# Mouse-Schematic_copy.net
KiCad netlist of a schematic drawn in EAGLE
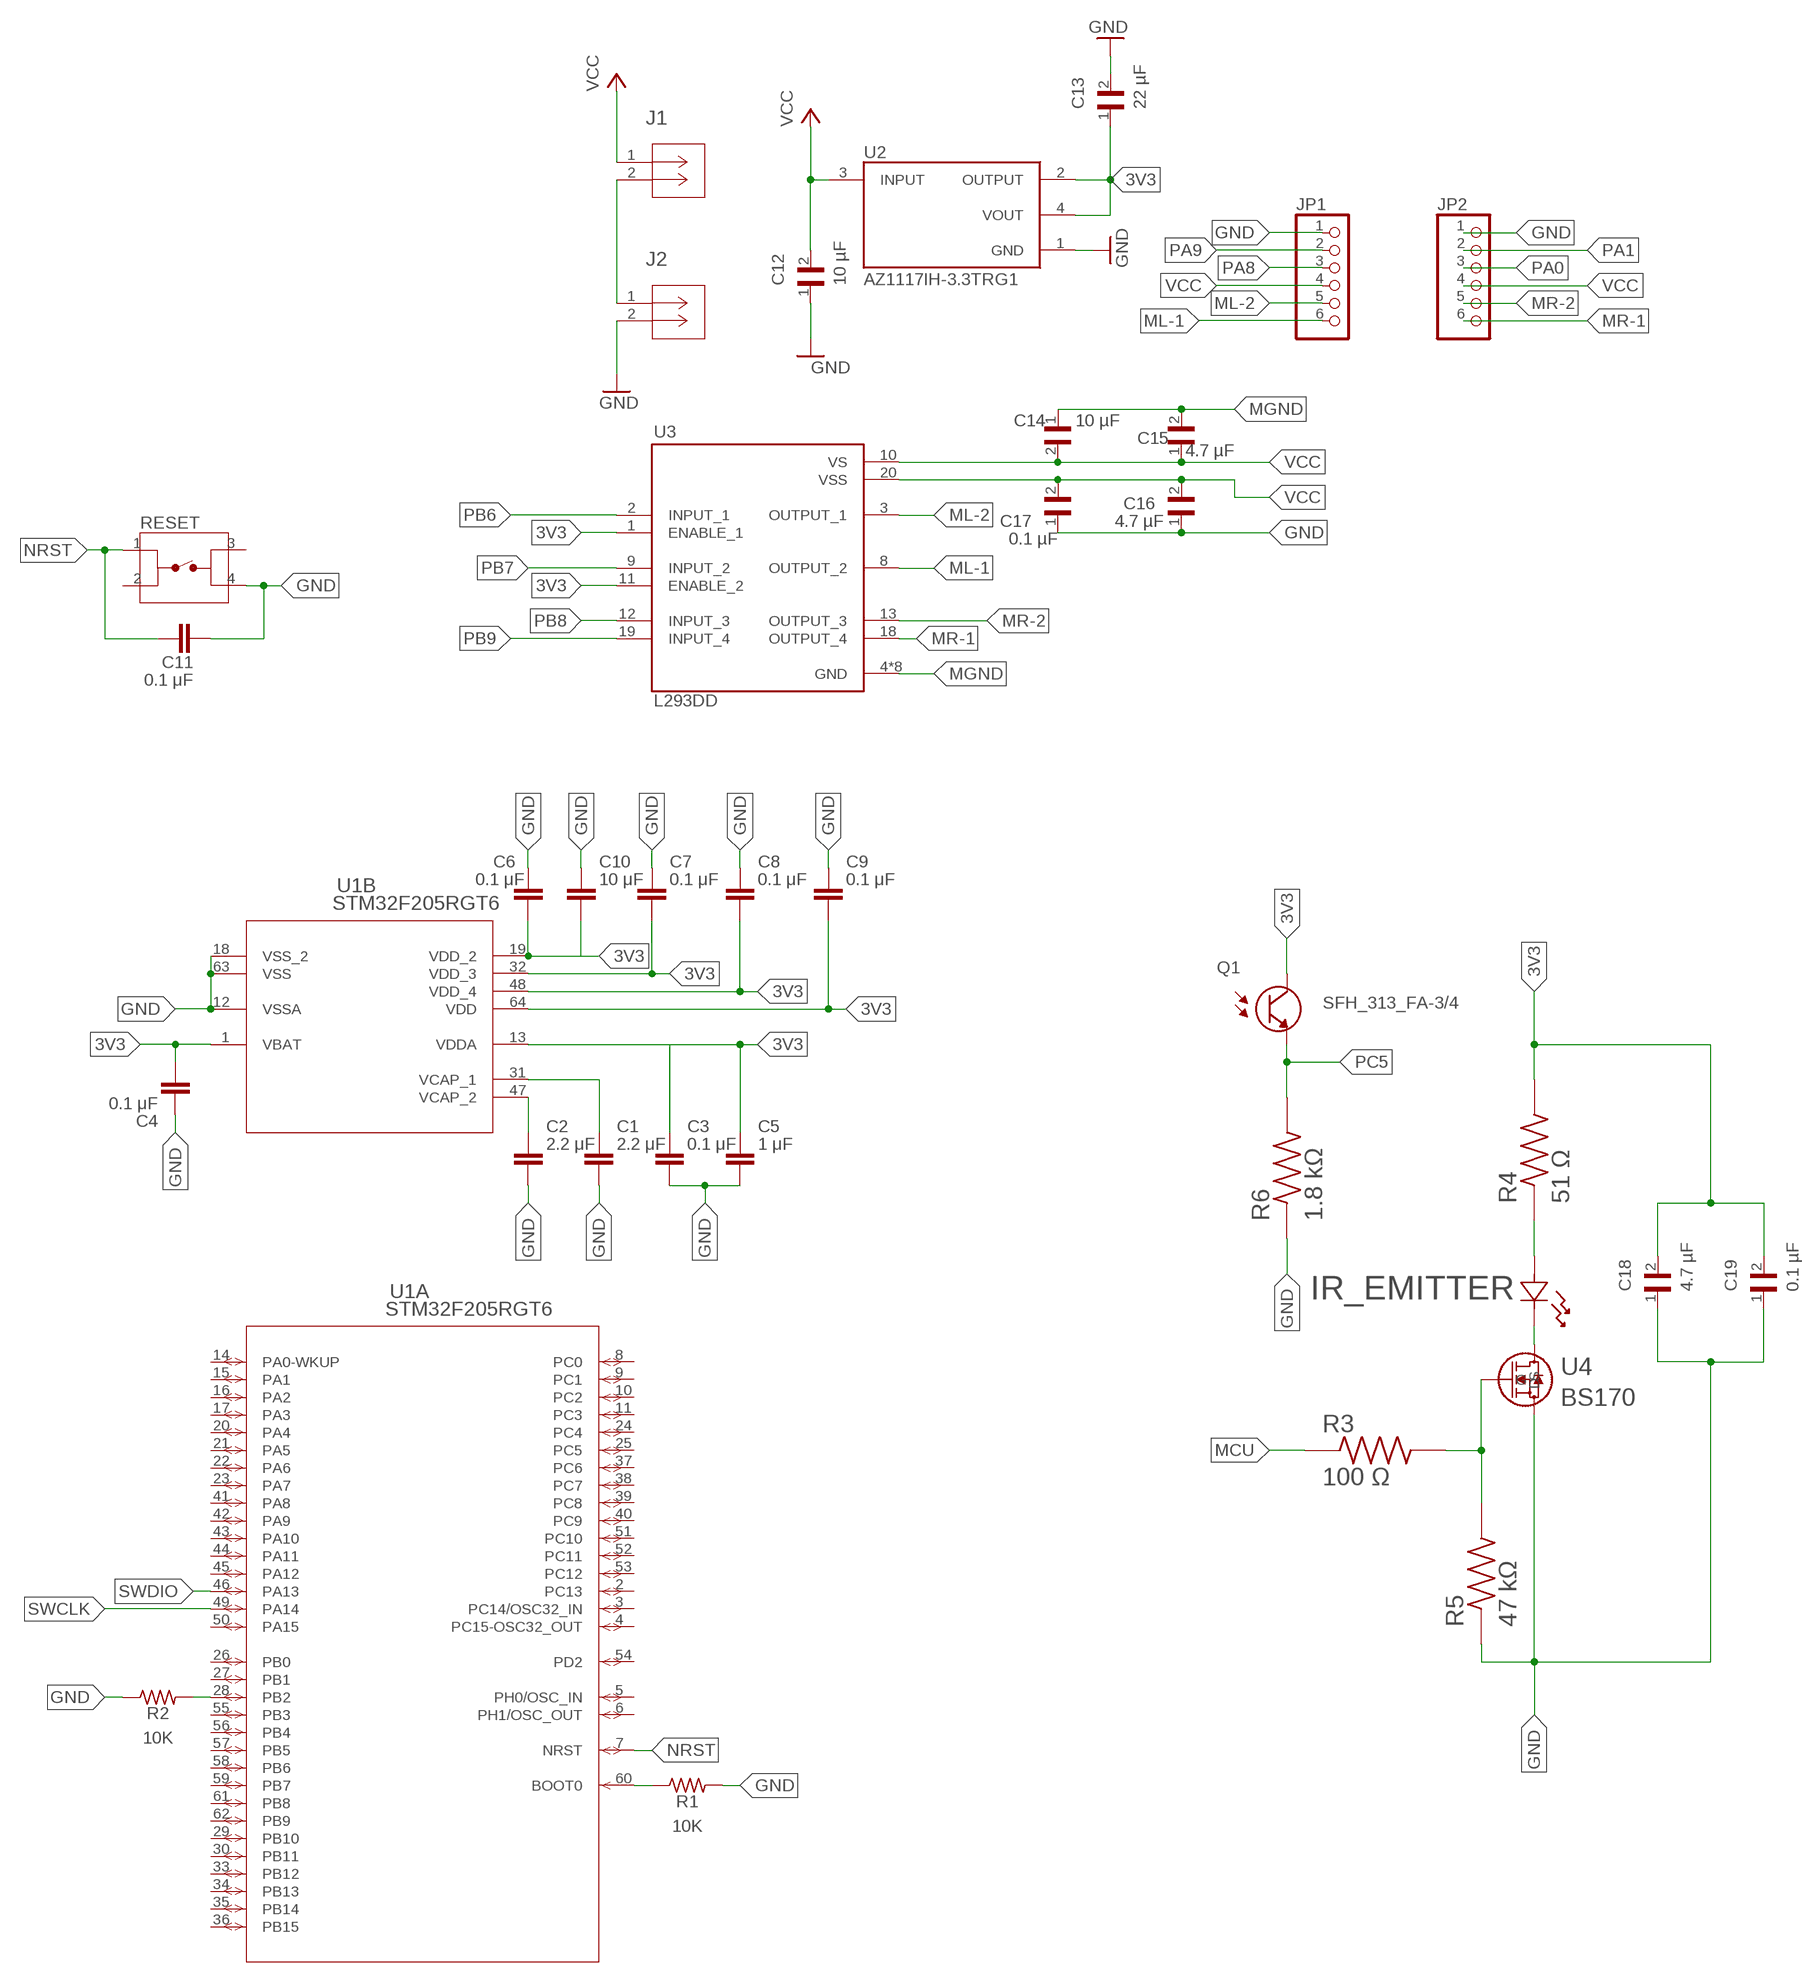
[diagram p0: schematic, sheet 1]

(export (version "E")
  (design (tool "Eeschema 10.0.6"))
  (components
    (comp (ref "C1")
      (value "2.2 μF")
      (footprint "eagle-import:CAPC1608X85")
      (libsource (lib "eagle-import") (part "CCHIP-0603(1608-METRIC)_"))
    )
    (comp (ref "C2")
      (value "2.2 μF")
      (footprint "eagle-import:CAPC1608X85")
      (libsource (lib "eagle-import") (part "CCHIP-0603(1608-METRIC)_"))
    )
    (comp (ref "C3")
      (value "0.1 μF")
      (footprint "eagle-import:CAPC1608X85")
      (libsource (lib "eagle-import") (part "CCHIP-0603(1608-METRIC)_"))
    )
    (comp (ref "C4")
      (value "0.1 μF")
      (footprint "eagle-import:CAPC1608X85")
      (libsource (lib "eagle-import") (part "CCHIP-0603(1608-METRIC)_"))
    )
    (comp (ref "C5")
      (value "1 μF")
      (footprint "eagle-import:CAPC1608X85")
      (libsource (lib "eagle-import") (part "CCHIP-0603(1608-METRIC)_"))
    )
    (comp (ref "C6")
      (value "0.1 μF")
      (footprint "eagle-import:CAPC1608X85")
      (libsource (lib "eagle-import") (part "CCHIP-0603(1608-METRIC)_"))
    )
    (comp (ref "C7")
      (value "0.1 μF")
      (footprint "eagle-import:CAPC1608X85")
      (libsource (lib "eagle-import") (part "Capacitor2_CCHIP-0603(1608-METRIC)_"))
    )
    (comp (ref "C8")
      (value "0.1 μF")
      (footprint "eagle-import:CAPC1608X85")
      (libsource (lib "eagle-import") (part "Capacitor2_CCHIP-0603(1608-METRIC)_"))
    )
    (comp (ref "C9")
      (value "0.1 μF")
      (footprint "eagle-import:CAPC1608X85")
      (libsource (lib "eagle-import") (part "Capacitor2_CCHIP-0603(1608-METRIC)_"))
    )
    (comp (ref "C10")
      (value "10 μF")
      (footprint "eagle-import:CAPC1608X85")
      (libsource (lib "eagle-import") (part "Capacitor2_CCHIP-0603(1608-METRIC)_"))
    )
    (comp (ref "C11")
      (value "0.1 μF")
      (footprint "eagle-import:CAPC1608X85")
      (libsource (lib "eagle-import") (part "Capacitor2_CCHIP-0603(1608-METRIC)_"))
    )
    (comp (ref "C12")
      (value "10 µF")
      (footprint "eagle-import:CAPC2012X135N")
      (fields (field (name "MF") "Murata") (field (name "MP") "GRM21BR61C106KE15L"))
      (libsource (lib "eagle-import") (part "GRM21BR61C106KE15L"))
    )
    (comp (ref "C13")
      (value "22 µF")
      (footprint "eagle-import:CAPC2012X145N")
      (fields (field (name "MF") "Murata") (field (name "MP") "GRM21BR61C226ME44L"))
      (libsource (lib "eagle-import") (part "GRM21BR61C226ME44L"))
    )
    (comp (ref "C14")
      (value "10 µF")
      (footprint "eagle-import:CAPC2012X135N")
      (fields (field (name "MF") "Murata") (field (name "MP") "GRM21BR61C106KE15L"))
      (libsource (lib "eagle-import") (part "GRM21BR61C106KE15L"))
    )
    (comp (ref "C15")
      (value "4.7 µF")
      (footprint "eagle-import:CAPC2012X140N")
      (fields
        (field (name "DIGIKEY_PART_NUMBER") "490-14466-2-ND")
        (field (name "MF") "Murata Electronics")
        (field (name "MP") "GRM21BR71C475KE51L")
      )
      (libsource (lib "eagle-import") (part "GRM21BR71C475KE51L"))
    )
    (comp (ref "C16")
      (value "4.7 µF")
      (footprint "eagle-import:CAPC2012X140N")
      (fields
        (field (name "DIGIKEY_PART_NUMBER") "490-14466-2-ND")
        (field (name "MF") "Murata Electronics")
        (field (name "MP") "GRM21BR71C475KE51L")
      )
      (libsource (lib "eagle-import") (part "GRM21BR71C475KE51L"))
    )
    (comp (ref "C17")
      (value "0.1 µF")
      (footprint "eagle-import:CAPC2012X140N")
      (fields (field (name "MF") "Murata") (field (name "MP") "GCM21BR72A104KA37K"))
      (libsource (lib "eagle-import") (part "GCM21BR72A104KA37K"))
    )
    (comp (ref "C18")
      (value "4.7 µF")
      (footprint "eagle-import:CAPC2012X140N")
      (fields
        (field (name "DIGIKEY_PART_NUMBER") "490-14466-2-ND")
        (field (name "MF") "Murata Electronics")
        (field (name "MP") "GRM21BR71C475KE51L")
      )
      (libsource (lib "eagle-import") (part "GRM21BR71C475KE51L"))
    )
    (comp (ref "C19")
      (value "0.1 µF")
      (footprint "eagle-import:CAPC2012X140N")
      (fields (field (name "MF") "Murata") (field (name "MP") "GCM21BR72A104KA37K"))
      (libsource (lib "eagle-import") (part "GCM21BR72A104KA37K"))
    )
    (comp (ref "J1")
      (value "B2B-PH-K-S")
      (footprint "eagle-import:CONN2_B2B-PH-K-S_JST")
      (fields (field (name "COPYRIGHT") "Copyright (C) 2023 Ultra Librarian. All rights reserved."))
      (libsource (lib "eagle-import") (part "B2B-PH-K-S"))
    )
    (comp (ref "J2")
      (value "B2B-PH-K-S")
      (footprint "eagle-import:CONN2_B2B-PH-K-S_JST")
      (fields (field (name "COPYRIGHT") "Copyright (C) 2023 Ultra Librarian. All rights reserved."))
      (libsource (lib "eagle-import") (part "B2B-PH-K-S"))
    )
    (comp (ref "JP1")
      (value "PINHD-1X6")
      (footprint "eagle-import:1X06")
      (libsource (lib "eagle-import") (part "PINHD-1X6"))
    )
    (comp (ref "JP2")
      (value "PINHD-1X6")
      (footprint "eagle-import:1X06")
      (libsource (lib "eagle-import") (part "PINHD-1X6"))
    )
    (comp (ref "LED1")
      (value "IR_EMITTER")
      (footprint "eagle-import:LED_INL-5AMIR15_INO")
      (fields
        (field (name "MANUFACTURER_PART_NUMBER") "INL-5AMIR15")
        (field (name "COPYRIGHT") "Copyright (C) 2024 Ultra Librarian. All rights reserved.")
      )
      (libsource (lib "eagle-import") (part "INL-5AMIR15"))
    )
    (comp (ref "Q1")
      (value "SFH_313_FA-3/4")
      (footprint "eagle-import:XDCR_SFH_313_FA-3_4")
      (fields
        (field (name "DIGIKEY_PART_NUMBER") "475-SFH313FA-3/4-ND")
        (field (name "MF") "OSRAM Opto")
        (field (name "MP") "SFH 313 FA-3/4")
      )
      (libsource (lib "eagle-import") (part "SFH_313_FA-3/4"))
    )
    (comp (ref "R1")
      (value "10K")
      (footprint "eagle-import:RESC1608X60")
      (libsource (lib "eagle-import") (part "R-USCHIP-0603(1608-METRIC)_"))
    )
    (comp (ref "R2")
      (value "10K")
      (footprint "eagle-import:RESC1608X60")
      (libsource (lib "eagle-import") (part "R-USCHIP-0603(1608-METRIC)_"))
    )
    (comp (ref "R3")
      (value "100 Ω")
      (footprint "eagle-import:RESC2012X60N")
      (fields
        (field (name "DIGIKEY_PART_NUMBER") "541-100TTR-ND")
        (field (name "MF") "Vishay")
        (field (name "MP") "CRCW0805100RFKEAHP")
      )
      (libsource (lib "eagle-import") (part "CRCW0805100RFKEAHP"))
    )
    (comp (ref "R4")
      (value "51 Ω")
      (footprint "eagle-import:RESC2012X60N")
      (fields
        (field (name "DIGIKEY_PART_NUMBER") "541-51.0TTR-ND")
        (field (name "MF") "Vishay")
        (field (name "MP") "CRCW080551R0FKEAHP")
      )
      (libsource (lib "eagle-import") (part "CRCW080551R0FKEAHP"))
    )
    (comp (ref "R5")
      (value "47 kΩ")
      (footprint "eagle-import:RESC2012X50N")
      (fields
        (field (name "DIGIKEY_PART_NUMBER") "541-47KATR-ND")
        (field (name "MF") "Vishay Dale")
        (field (name "MP") "CRCW080547K0JNEA")
      )
      (libsource (lib "eagle-import") (part "CRCW080547K0JNEA"))
    )
    (comp (ref "R6")
      (value "1.8 kΩ")
      (footprint "eagle-import:RESC2012X50N")
      (fields
        (field (name "DIGIKEY_PART_NUMBER") "541-CRCW08051K80FKEBTR-ND")
        (field (name "MF") "Vishay Dale")
        (field (name "MP") "CRCW08051K80FKEB")
      )
      (libsource (lib "eagle-import") (part "CRCW08051K80FKEB"))
    )
    (comp (ref "RESET")
      (value "FSM4JSMA")
      (footprint "eagle-import:TE_FSM4JSMA")
      (fields
        (field (name "COMMENT") "4-1437565-1")
        (field (name "DIGI-KEY_PART_NUMBER") "450-1759-2-ND")
        (field (name "MF") "TE Connectivity")
      )
      (libsource (lib "eagle-import") (part "FSM4JSMA"))
    )
    (comp (ref "U1")
      (value "STM32F205RGT6")
      (footprint "eagle-import:LQFP64-10X10MM")
      (fields (field (name "COPYRIGHT") "Copyright (C) 2021 Ultra Librarian. All rights reserved."))
      (libsource (lib "eagle-import") (part "STM32F205RGT6"))
    )
    (comp (ref "U2")
      (value "AZ1117IH-3.3TRG1")
      (footprint "eagle-import:SOT230P700X185-4N")
      (fields (field (name "MF") "Diodes Inc."))
      (libsource (lib "eagle-import") (part "AZ1117IH-3.3TRG1"))
    )
    (comp (ref "U3")
      (value "L293DD")
      (footprint "eagle-import:SOIC127P1032X265-20N")
      (fields (field (name "DIGIKEY_PART_NUMBER") "497-1390-5-ND") (field (name "MF") "STMicroelectronics"))
      (libsource (lib "eagle-import") (part "L293DD"))
    )
    (comp (ref "U4")
      (value "BS170")
      (footprint "eagle-import:TO_SA06_ONS")
      (fields (field (name "COPYRIGHT") "Copyright (C) 2024 Ultra Librarian. All rights reserved."))
      (libsource (lib "eagle-import") (part "BS170"))
    )
  )
  (nets
    (net (code "1") (name "3V3") (class "Default")
      (node (ref "C10") (pin "2") (pinfunction "2_2") (pintype "passive"))
      (node (ref "C13") (pin "1") (pinfunction "1_1") (pintype "passive"))
      (node (ref "C18") (pin "2") (pinfunction "2_2") (pintype "passive"))
      (node (ref "C19") (pin "2") (pinfunction "2_2") (pintype "passive"))
      (node (ref "C3") (pin "1") (pinfunction "1_1") (pintype "passive"))
      (node (ref "C4") (pin "2") (pinfunction "2_2") (pintype "passive"))
      (node (ref "C5") (pin "1") (pinfunction "1_1") (pintype "passive"))
      (node (ref "C6") (pin "2") (pinfunction "2_2") (pintype "passive"))
      (node (ref "C7") (pin "2") (pinfunction "2_2") (pintype "passive"))
      (node (ref "C8") (pin "2") (pinfunction "2_2") (pintype "passive"))
      (node (ref "C9") (pin "2") (pinfunction "2_2") (pintype "passive"))
      (node (ref "Q1") (pin "2") (pinfunction "C_2") (pintype "passive"))
      (node (ref "R4") (pin "2") (pinfunction "2_2") (pintype "passive"))
      (node (ref "U1") (pin "1") (pinfunction "VBAT_1") (pintype "power_in"))
      (node (ref "U1") (pin "13") (pinfunction "VDDA_13") (pintype "power_in"))
      (node (ref "U1") (pin "19") (pinfunction "VDD_2_19") (pintype "power_in"))
      (node (ref "U1") (pin "32") (pinfunction "VDD_3_32") (pintype "power_in"))
      (node (ref "U1") (pin "48") (pinfunction "VDD_4_48") (pintype "power_in"))
      (node (ref "U1") (pin "64") (pinfunction "VDD_64") (pintype "power_in"))
      (node (ref "U2") (pin "2") (pinfunction "OUTPUT_2") (pintype "output"))
      (node (ref "U2") (pin "4") (pinfunction "VOUT_4") (pintype "output"))
      (node (ref "U3") (pin "1") (pinfunction "ENABLE_1_1") (pintype "input"))
      (node (ref "U3") (pin "11") (pinfunction "ENABLE_2_11") (pintype "input"))
    )
    (net (code "2") (name "GND") (class "Default")
      (node (ref "C1") (pin "2") (pinfunction "2_2") (pintype "passive"))
      (node (ref "C10") (pin "1") (pinfunction "1_1") (pintype "passive"))
      (node (ref "C11") (pin "2") (pinfunction "2_2") (pintype "passive"))
      (node (ref "C12") (pin "1") (pinfunction "1_1") (pintype "passive"))
      (node (ref "C13") (pin "2") (pinfunction "2_2") (pintype "passive"))
      (node (ref "C16") (pin "1") (pinfunction "1_1") (pintype "passive"))
      (node (ref "C17") (pin "1") (pinfunction "1_1") (pintype "passive"))
      (node (ref "C18") (pin "1") (pinfunction "1_1") (pintype "passive"))
      (node (ref "C19") (pin "1") (pinfunction "1_1") (pintype "passive"))
      (node (ref "C2") (pin "2") (pinfunction "2_2") (pintype "passive"))
      (node (ref "C3") (pin "2") (pinfunction "2_2") (pintype "passive"))
      (node (ref "C4") (pin "1") (pinfunction "1_1") (pintype "passive"))
      (node (ref "C5") (pin "2") (pinfunction "2_2") (pintype "passive"))
      (node (ref "C6") (pin "1") (pinfunction "1_1") (pintype "passive"))
      (node (ref "C7") (pin "1") (pinfunction "1_1") (pintype "passive"))
      (node (ref "C8") (pin "1") (pinfunction "1_1") (pintype "passive"))
      (node (ref "C9") (pin "1") (pinfunction "1_1") (pintype "passive"))
      (node (ref "J2") (pin "2") (pinfunction "2_2") (pintype "passive"))
      (node (ref "JP1") (pin "1") (pinfunction "1_1") (pintype "passive"))
      (node (ref "JP2") (pin "1") (pinfunction "1_1") (pintype "passive"))
      (node (ref "R1") (pin "2") (pinfunction "2_2") (pintype "passive"))
      (node (ref "R2") (pin "1") (pinfunction "1_1") (pintype "passive"))
      (node (ref "R5") (pin "1") (pinfunction "1_1") (pintype "passive"))
      (node (ref "R6") (pin "1") (pinfunction "1_1") (pintype "passive"))
      (node (ref "RESET") (pin "4") (pinfunction "4_4") (pintype "passive"))
      (node (ref "U1") (pin "12") (pinfunction "VSSA_12") (pintype "power_in"))
      (node (ref "U1") (pin "18") (pinfunction "VSS_2_18") (pintype "power_in"))
      (node (ref "U1") (pin "63") (pinfunction "VSS_63") (pintype "power_in"))
      (node (ref "U2") (pin "1") (pinfunction "GND_1") (pintype "power_in"))
      (node (ref "U4") (pin "3") (pinfunction "S_3") (pintype "passive"))
    )
    (net (code "3") (name "MCU") (class "Default")
      (node (ref "R3") (pin "1") (pinfunction "1_1") (pintype "passive"))
    )
    (net (code "4") (name "MGND") (class "Default")
      (node (ref "C14") (pin "1") (pinfunction "1_1") (pintype "passive"))
      (node (ref "C15") (pin "2") (pinfunction "2_2") (pintype "passive"))
      (node (ref "U3") (pin "14") (pinfunction "GND_14") (pintype "power_in"))
      (node (ref "U3") (pin "15") (pinfunction "GND_15") (pintype "power_in"))
      (node (ref "U3") (pin "16") (pinfunction "GND_16") (pintype "power_in"))
      (node (ref "U3") (pin "17") (pinfunction "GND_17") (pintype "power_in"))
      (node (ref "U3") (pin "4") (pinfunction "GND_4") (pintype "power_in"))
      (node (ref "U3") (pin "5") (pinfunction "GND_5") (pintype "power_in"))
      (node (ref "U3") (pin "6") (pinfunction "GND_6") (pintype "power_in"))
      (node (ref "U3") (pin "7") (pinfunction "GND_7") (pintype "power_in"))
    )
    (net (code "5") (name "ML-1") (class "Default")
      (node (ref "JP1") (pin "6") (pinfunction "6_6") (pintype "passive"))
      (node (ref "U3") (pin "8") (pinfunction "OUTPUT_2_8") (pintype "output"))
    )
    (net (code "6") (name "ML-2") (class "Default")
      (node (ref "JP1") (pin "5") (pinfunction "5_5") (pintype "passive"))
      (node (ref "U3") (pin "3") (pinfunction "OUTPUT_1_3") (pintype "output"))
    )
    (net (code "7") (name "MR-1") (class "Default")
      (node (ref "JP2") (pin "6") (pinfunction "6_6") (pintype "passive"))
      (node (ref "U3") (pin "18") (pinfunction "OUTPUT_4_18") (pintype "output"))
    )
    (net (code "8") (name "MR-2") (class "Default")
      (node (ref "JP2") (pin "5") (pinfunction "5_5") (pintype "passive"))
      (node (ref "U3") (pin "13") (pinfunction "OUTPUT_3_13") (pintype "output"))
    )
    (net (code "9") (name "NRST") (class "Default")
      (node (ref "C11") (pin "1") (pinfunction "1_1") (pintype "passive"))
      (node (ref "RESET") (pin "1") (pinfunction "1_1") (pintype "passive"))
      (node (ref "U1") (pin "7") (pinfunction "NRST_7") (pintype "bidirectional"))
    )
    (net (code "10") (name "Net-(J1-Pad2)") (class "Default")
      (node (ref "J1") (pin "2") (pinfunction "2_2") (pintype "passive"))
      (node (ref "J2") (pin "1") (pinfunction "1_1") (pintype "passive"))
    )
    (net (code "11") (name "Net-(LED1-Pad2)") (class "Default")
      (node (ref "LED1") (pin "2") (pinfunction "2_2") (pintype "passive"))
      (node (ref "R4") (pin "1") (pinfunction "1_1") (pintype "passive"))
    )
    (net (code "12") (name "Net-(U1A-BOOT0)") (class "Default")
      (node (ref "R1") (pin "1") (pinfunction "1_1") (pintype "passive"))
      (node (ref "U1") (pin "60") (pinfunction "BOOT0_60") (pintype "input"))
    )
    (net (code "13") (name "Net-(U1A-PB2)") (class "Default")
      (node (ref "R2") (pin "2") (pinfunction "2_2") (pintype "passive"))
      (node (ref "U1") (pin "28") (pinfunction "PB2_28") (pintype "bidirectional"))
    )
    (net (code "14") (name "Net-(U1B-VCAP_1)") (class "Default")
      (node (ref "C1") (pin "1") (pinfunction "1_1") (pintype "passive"))
      (node (ref "U1") (pin "31") (pinfunction "VCAP_1_31") (pintype "power_in"))
    )
    (net (code "15") (name "Net-(U1B-VCAP_2)") (class "Default")
      (node (ref "C2") (pin "1") (pinfunction "1_1") (pintype "passive"))
      (node (ref "U1") (pin "47") (pinfunction "VCAP_2_47") (pintype "power_in"))
    )
    (net (code "16") (name "Net-(U4-D)") (class "Default")
      (node (ref "LED1") (pin "1") (pinfunction "1_1") (pintype "passive"))
      (node (ref "U4") (pin "2") (pinfunction "D_2") (pintype "passive"))
    )
    (net (code "17") (name "Net-(U4-G)") (class "Default")
      (node (ref "R3") (pin "2") (pinfunction "2_2") (pintype "passive"))
      (node (ref "R5") (pin "2") (pinfunction "2_2") (pintype "passive"))
      (node (ref "U4") (pin "1") (pinfunction "G_1") (pintype "passive"))
    )
    (net (code "18") (name "PA0") (class "Default")
      (node (ref "JP2") (pin "3") (pinfunction "3_3") (pintype "passive"))
    )
    (net (code "19") (name "PA1") (class "Default")
      (node (ref "JP2") (pin "2") (pinfunction "2_2") (pintype "passive"))
    )
    (net (code "20") (name "PA8") (class "Default")
      (node (ref "JP1") (pin "3") (pinfunction "3_3") (pintype "passive"))
    )
    (net (code "21") (name "PA9") (class "Default")
      (node (ref "JP1") (pin "2") (pinfunction "2_2") (pintype "passive"))
    )
    (net (code "22") (name "PB6") (class "Default")
      (node (ref "U3") (pin "2") (pinfunction "INPUT_1_2") (pintype "input"))
    )
    (net (code "23") (name "PB7") (class "Default")
      (node (ref "U3") (pin "9") (pinfunction "INPUT_2_9") (pintype "input"))
    )
    (net (code "24") (name "PB8") (class "Default")
      (node (ref "U3") (pin "12") (pinfunction "INPUT_3_12") (pintype "input"))
    )
    (net (code "25") (name "PB9") (class "Default")
      (node (ref "U3") (pin "19") (pinfunction "INPUT_4_19") (pintype "input"))
    )
    (net (code "26") (name "PC5") (class "Default")
      (node (ref "Q1") (pin "1") (pinfunction "E_1") (pintype "passive"))
      (node (ref "R6") (pin "2") (pinfunction "2_2") (pintype "passive"))
    )
    (net (code "27") (name "SWCLK") (class "Default")
      (node (ref "U1") (pin "49") (pinfunction "PA14_49") (pintype "bidirectional"))
    )
    (net (code "28") (name "SWDIO") (class "Default")
      (node (ref "U1") (pin "46") (pinfunction "PA13_46") (pintype "bidirectional"))
    )
    (net (code "29") (name "VCC") (class "Default")
      (node (ref "C12") (pin "2") (pinfunction "2_2") (pintype "passive"))
      (node (ref "C14") (pin "2") (pinfunction "2_2") (pintype "passive"))
      (node (ref "C15") (pin "1") (pinfunction "1_1") (pintype "passive"))
      (node (ref "C16") (pin "2") (pinfunction "2_2") (pintype "passive"))
      (node (ref "C17") (pin "2") (pinfunction "2_2") (pintype "passive"))
      (node (ref "J1") (pin "1") (pinfunction "1_1") (pintype "passive"))
      (node (ref "JP1") (pin "4") (pinfunction "4_4") (pintype "passive"))
      (node (ref "JP2") (pin "4") (pinfunction "4_4") (pintype "passive"))
      (node (ref "U2") (pin "3") (pinfunction "INPUT_3") (pintype "input"))
      (node (ref "U3") (pin "10") (pinfunction "VS_10") (pintype "power_in"))
      (node (ref "U3") (pin "20") (pinfunction "VSS_20") (pintype "power_in"))
    )
    (net (code "30") (name "unconnected-(RESET-Pad2)") (class "Default")
      (node (ref "RESET") (pin "2") (pinfunction "2_2") (pintype "passive"))
    )
    (net (code "31") (name "unconnected-(RESET-Pad3)") (class "Default")
      (node (ref "RESET") (pin "3") (pinfunction "3_3") (pintype "passive"))
    )
    (net (code "32") (name "unconnected-(U1A-PA0-WKUP-Pad14)") (class "Default")
      (node (ref "U1") (pin "14") (pinfunction "PA0-WKUP_14") (pintype "bidirectional"))
    )
    (net (code "33") (name "unconnected-(U1A-PA1-Pad15)") (class "Default")
      (node (ref "U1") (pin "15") (pinfunction "PA1_15") (pintype "bidirectional"))
    )
    (net (code "34") (name "unconnected-(U1A-PA2-Pad16)") (class "Default")
      (node (ref "U1") (pin "16") (pinfunction "PA2_16") (pintype "bidirectional"))
    )
    (net (code "35") (name "unconnected-(U1A-PA3-Pad17)") (class "Default")
      (node (ref "U1") (pin "17") (pinfunction "PA3_17") (pintype "bidirectional"))
    )
    (net (code "36") (name "unconnected-(U1A-PA4-Pad20)") (class "Default")
      (node (ref "U1") (pin "20") (pinfunction "PA4_20") (pintype "bidirectional"))
    )
    (net (code "37") (name "unconnected-(U1A-PA5-Pad21)") (class "Default")
      (node (ref "U1") (pin "21") (pinfunction "PA5_21") (pintype "bidirectional"))
    )
    (net (code "38") (name "unconnected-(U1A-PA6-Pad22)") (class "Default")
      (node (ref "U1") (pin "22") (pinfunction "PA6_22") (pintype "bidirectional"))
    )
    (net (code "39") (name "unconnected-(U1A-PA7-Pad23)") (class "Default")
      (node (ref "U1") (pin "23") (pinfunction "PA7_23") (pintype "bidirectional"))
    )
    (net (code "40") (name "unconnected-(U1A-PA8-Pad41)") (class "Default")
      (node (ref "U1") (pin "41") (pinfunction "PA8_41") (pintype "bidirectional"))
    )
    (net (code "41") (name "unconnected-(U1A-PA9-Pad42)") (class "Default")
      (node (ref "U1") (pin "42") (pinfunction "PA9_42") (pintype "bidirectional"))
    )
    (net (code "42") (name "unconnected-(U1A-PA10-Pad43)") (class "Default")
      (node (ref "U1") (pin "43") (pinfunction "PA10_43") (pintype "bidirectional"))
    )
    (net (code "43") (name "unconnected-(U1A-PA11-Pad44)") (class "Default")
      (node (ref "U1") (pin "44") (pinfunction "PA11_44") (pintype "bidirectional"))
    )
    (net (code "44") (name "unconnected-(U1A-PA12-Pad45)") (class "Default")
      (node (ref "U1") (pin "45") (pinfunction "PA12_45") (pintype "bidirectional"))
    )
    (net (code "45") (name "unconnected-(U1A-PA15-Pad50)") (class "Default")
      (node (ref "U1") (pin "50") (pinfunction "PA15_50") (pintype "bidirectional"))
    )
    (net (code "46") (name "unconnected-(U1A-PB0-Pad26)") (class "Default")
      (node (ref "U1") (pin "26") (pinfunction "PB0_26") (pintype "bidirectional"))
    )
    (net (code "47") (name "unconnected-(U1A-PB1-Pad27)") (class "Default")
      (node (ref "U1") (pin "27") (pinfunction "PB1_27") (pintype "bidirectional"))
    )
    (net (code "48") (name "unconnected-(U1A-PB3-Pad55)") (class "Default")
      (node (ref "U1") (pin "55") (pinfunction "PB3_55") (pintype "bidirectional"))
    )
    (net (code "49") (name "unconnected-(U1A-PB4-Pad56)") (class "Default")
      (node (ref "U1") (pin "56") (pinfunction "PB4_56") (pintype "bidirectional"))
    )
    (net (code "50") (name "unconnected-(U1A-PB5-Pad57)") (class "Default")
      (node (ref "U1") (pin "57") (pinfunction "PB5_57") (pintype "bidirectional"))
    )
    (net (code "51") (name "unconnected-(U1A-PB6-Pad58)") (class "Default")
      (node (ref "U1") (pin "58") (pinfunction "PB6_58") (pintype "bidirectional"))
    )
    (net (code "52") (name "unconnected-(U1A-PB7-Pad59)") (class "Default")
      (node (ref "U1") (pin "59") (pinfunction "PB7_59") (pintype "bidirectional"))
    )
    (net (code "53") (name "unconnected-(U1A-PB8-Pad61)") (class "Default")
      (node (ref "U1") (pin "61") (pinfunction "PB8_61") (pintype "bidirectional"))
    )
    (net (code "54") (name "unconnected-(U1A-PB9-Pad62)") (class "Default")
      (node (ref "U1") (pin "62") (pinfunction "PB9_62") (pintype "bidirectional"))
    )
    (net (code "55") (name "unconnected-(U1A-PB10-Pad29)") (class "Default")
      (node (ref "U1") (pin "29") (pinfunction "PB10_29") (pintype "bidirectional"))
    )
    (net (code "56") (name "unconnected-(U1A-PB11-Pad30)") (class "Default")
      (node (ref "U1") (pin "30") (pinfunction "PB11_30") (pintype "bidirectional"))
    )
    (net (code "57") (name "unconnected-(U1A-PB12-Pad33)") (class "Default")
      (node (ref "U1") (pin "33") (pinfunction "PB12_33") (pintype "bidirectional"))
    )
    (net (code "58") (name "unconnected-(U1A-PB13-Pad34)") (class "Default")
      (node (ref "U1") (pin "34") (pinfunction "PB13_34") (pintype "bidirectional"))
    )
    (net (code "59") (name "unconnected-(U1A-PB14-Pad35)") (class "Default")
      (node (ref "U1") (pin "35") (pinfunction "PB14_35") (pintype "bidirectional"))
    )
    (net (code "60") (name "unconnected-(U1A-PB15-Pad36)") (class "Default")
      (node (ref "U1") (pin "36") (pinfunction "PB15_36") (pintype "bidirectional"))
    )
    (net (code "61") (name "unconnected-(U1A-PC0-Pad8)") (class "Default")
      (node (ref "U1") (pin "8") (pinfunction "PC0_8") (pintype "bidirectional"))
    )
    (net (code "62") (name "unconnected-(U1A-PC1-Pad9)") (class "Default")
      (node (ref "U1") (pin "9") (pinfunction "PC1_9") (pintype "bidirectional"))
    )
    (net (code "63") (name "unconnected-(U1A-PC2-Pad10)") (class "Default")
      (node (ref "U1") (pin "10") (pinfunction "PC2_10") (pintype "bidirectional"))
    )
    (net (code "64") (name "unconnected-(U1A-PC3-Pad11)") (class "Default")
      (node (ref "U1") (pin "11") (pinfunction "PC3_11") (pintype "bidirectional"))
    )
    (net (code "65") (name "unconnected-(U1A-PC4-Pad24)") (class "Default")
      (node (ref "U1") (pin "24") (pinfunction "PC4_24") (pintype "bidirectional"))
    )
    (net (code "66") (name "unconnected-(U1A-PC5-Pad25)") (class "Default")
      (node (ref "U1") (pin "25") (pinfunction "PC5_25") (pintype "bidirectional"))
    )
    (net (code "67") (name "unconnected-(U1A-PC6-Pad37)") (class "Default")
      (node (ref "U1") (pin "37") (pinfunction "PC6_37") (pintype "bidirectional"))
    )
    (net (code "68") (name "unconnected-(U1A-PC7-Pad38)") (class "Default")
      (node (ref "U1") (pin "38") (pinfunction "PC7_38") (pintype "bidirectional"))
    )
    (net (code "69") (name "unconnected-(U1A-PC8-Pad39)") (class "Default")
      (node (ref "U1") (pin "39") (pinfunction "PC8_39") (pintype "bidirectional"))
    )
    (net (code "70") (name "unconnected-(U1A-PC9-Pad40)") (class "Default")
      (node (ref "U1") (pin "40") (pinfunction "PC9_40") (pintype "bidirectional"))
    )
    (net (code "71") (name "unconnected-(U1A-PC10-Pad51)") (class "Default")
      (node (ref "U1") (pin "51") (pinfunction "PC10_51") (pintype "bidirectional"))
    )
    (net (code "72") (name "unconnected-(U1A-PC11-Pad52)") (class "Default")
      (node (ref "U1") (pin "52") (pinfunction "PC11_52") (pintype "bidirectional"))
    )
    (net (code "73") (name "unconnected-(U1A-PC12-Pad53)") (class "Default")
      (node (ref "U1") (pin "53") (pinfunction "PC12_53") (pintype "bidirectional"))
    )
    (net (code "74") (name "unconnected-(U1A-PC13-Pad2)") (class "Default")
      (node (ref "U1") (pin "2") (pinfunction "PC13_2") (pintype "bidirectional"))
    )
    (net (code "75") (name "unconnected-(U1A-PC14{slash}OSC32_IN-Pad3)") (class "Default")
      (node (ref "U1") (pin "3") (pinfunction "PC14/OSC32_IN_3") (pintype "bidirectional"))
    )
    (net (code "76") (name "unconnected-(U1A-PC15-OSC32_OUT-Pad4)") (class "Default")
      (node (ref "U1") (pin "4") (pinfunction "PC15-OSC32_OUT_4") (pintype "bidirectional"))
    )
    (net (code "77") (name "unconnected-(U1A-PD2-Pad54)") (class "Default")
      (node (ref "U1") (pin "54") (pinfunction "PD2_54") (pintype "bidirectional"))
    )
    (net (code "78") (name "unconnected-(U1A-PH0{slash}OSC_IN-Pad5)") (class "Default")
      (node (ref "U1") (pin "5") (pinfunction "PH0/OSC_IN_5") (pintype "bidirectional"))
    )
    (net (code "79") (name "unconnected-(U1A-PH1{slash}OSC_OUT-Pad6)") (class "Default")
      (node (ref "U1") (pin "6") (pinfunction "PH1/OSC_OUT_6") (pintype "bidirectional"))
    )
  )
)
